# InkTime.net
KiCad netlist of a schematic drawn in EAGLE
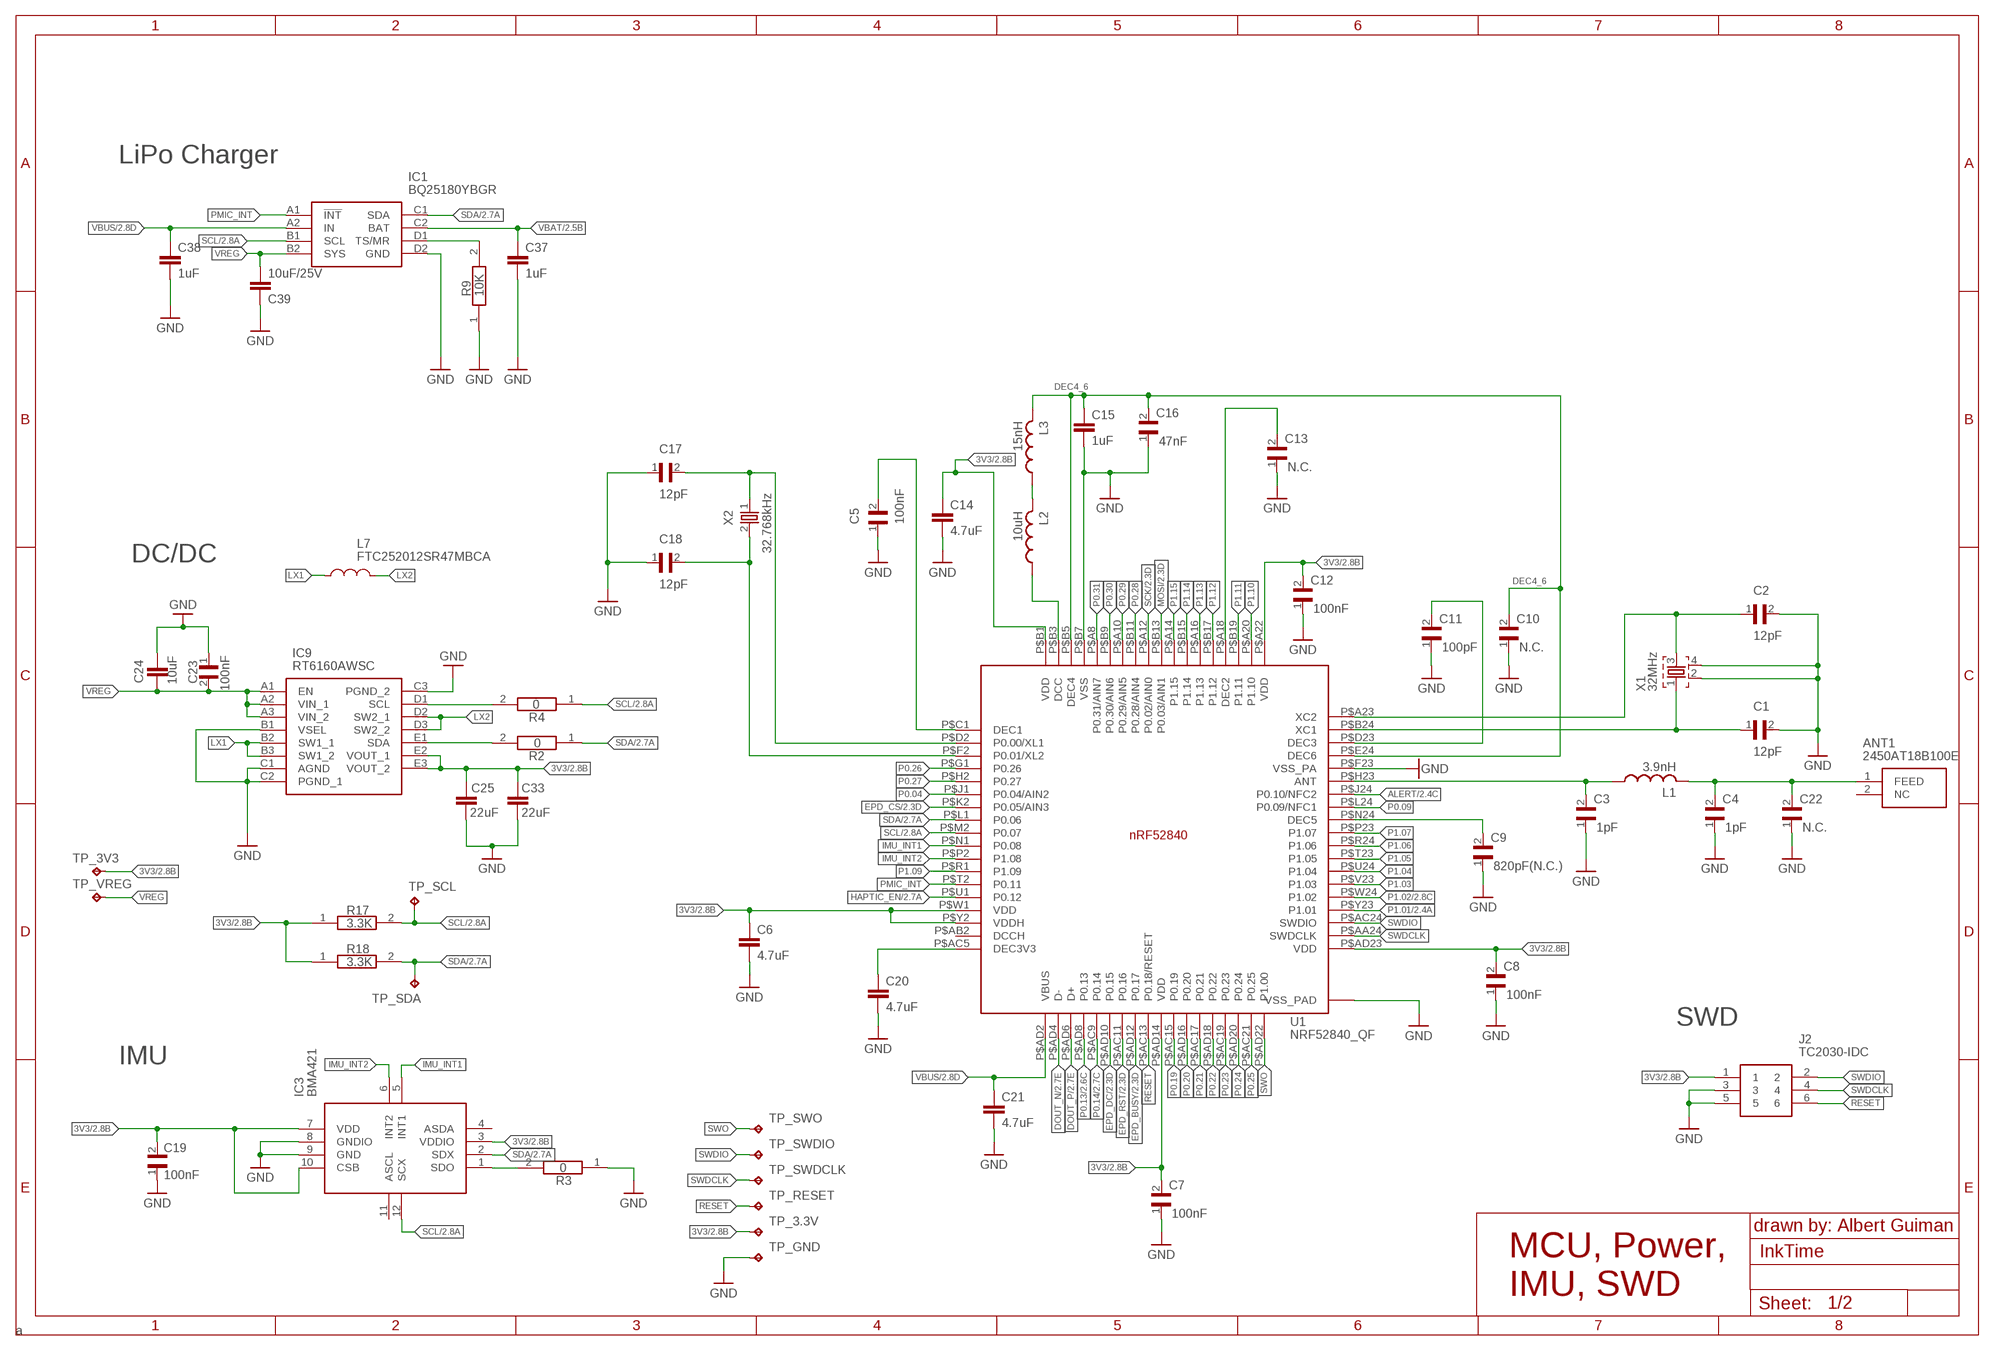
[diagram p0: schematic, sheet 1]
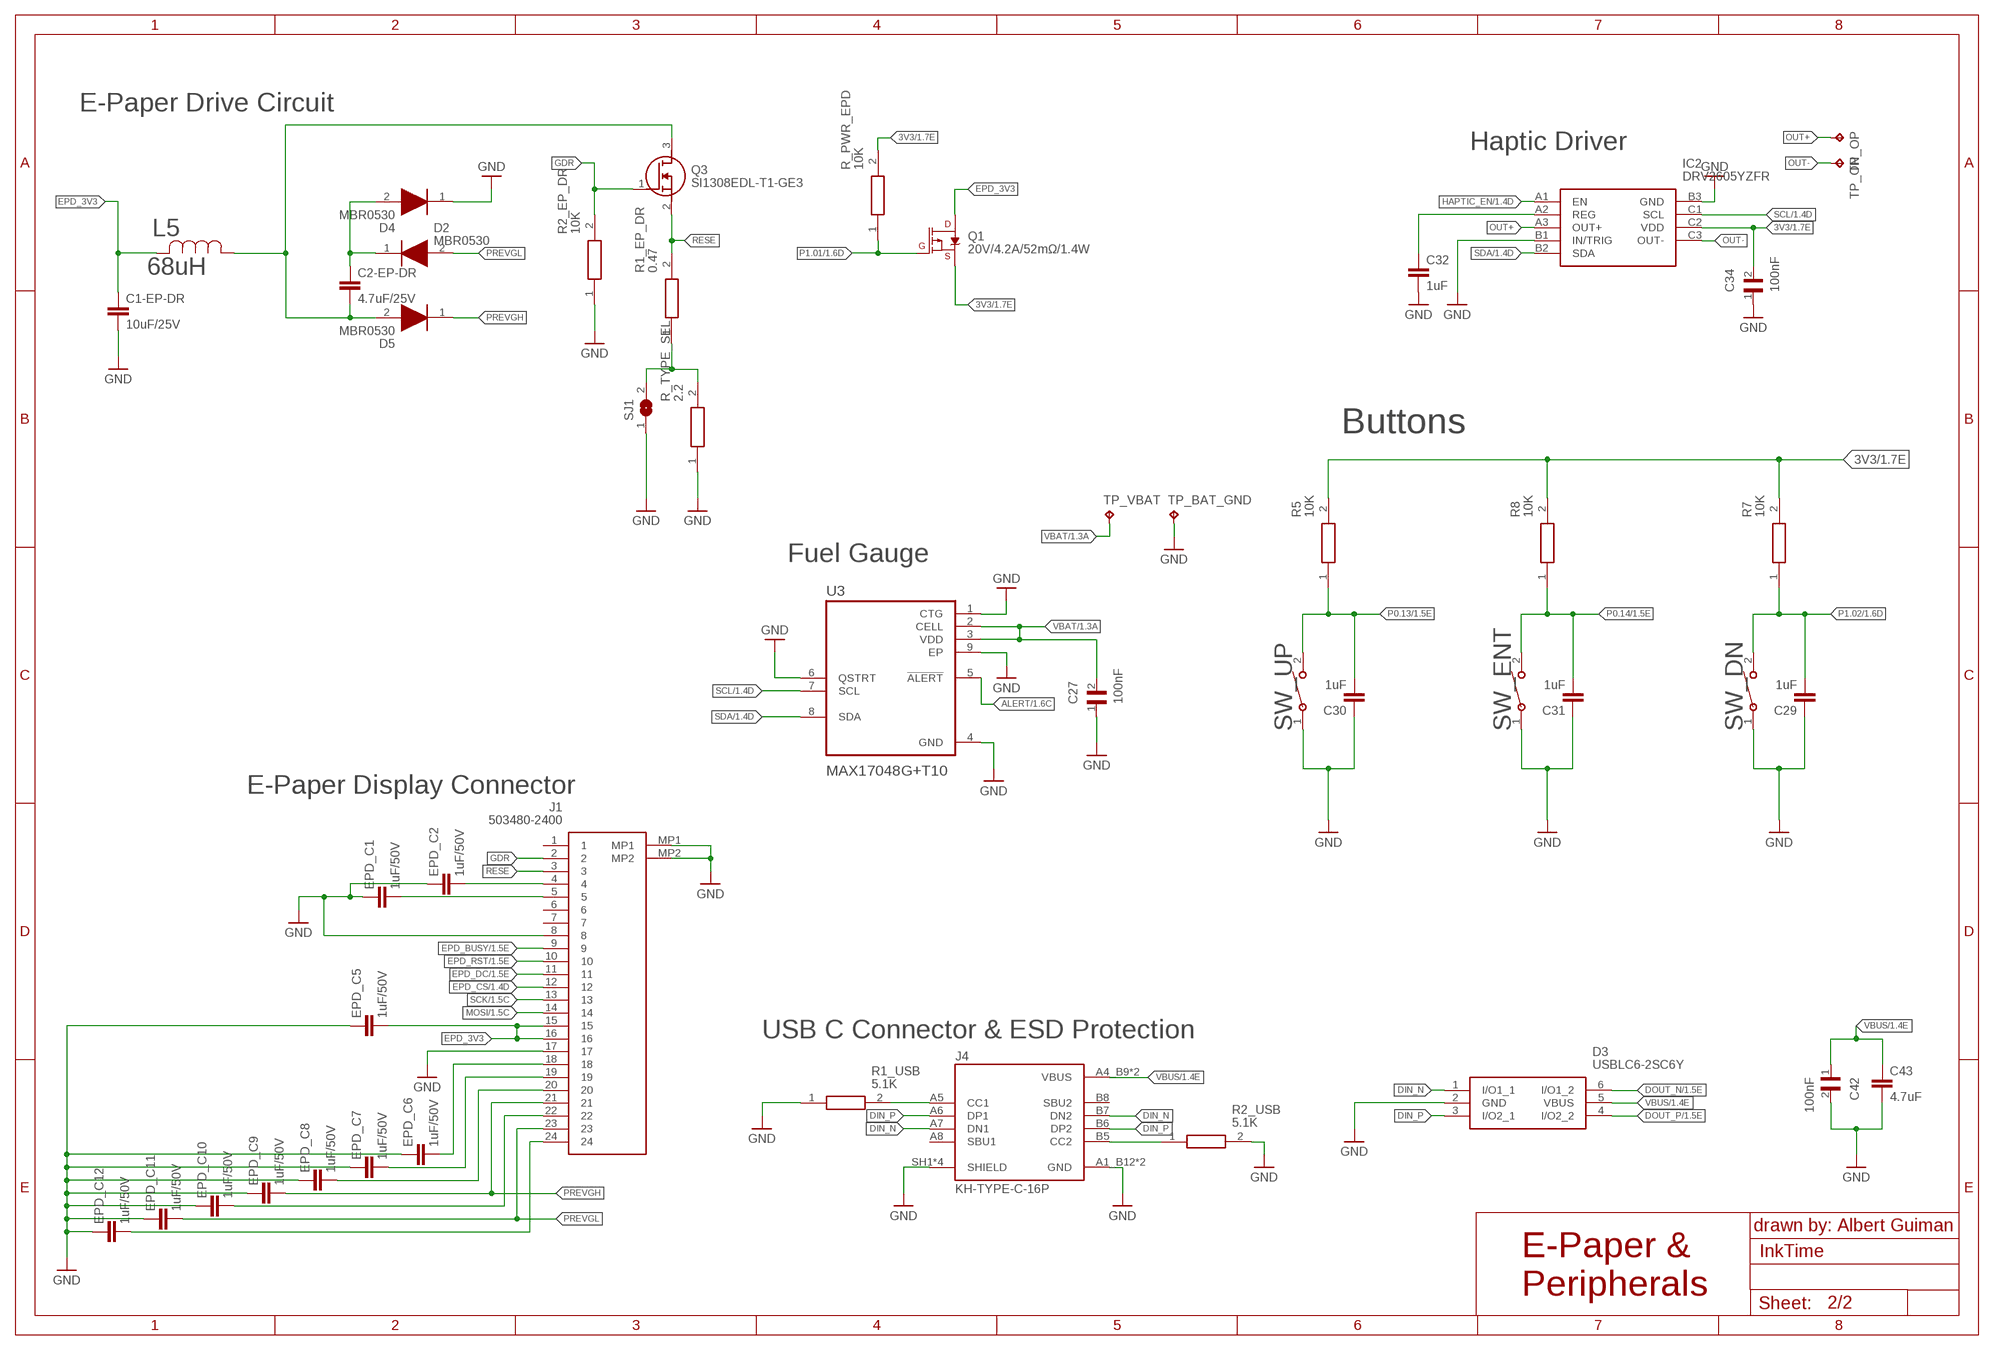
[diagram p1: schematic, sheet 2]

(export (version "E")
  (design (tool "Eeschema 10.0.6"))
  (components
    (comp (ref "C1-EP-DR")
      (value "10uF/25V")
      (footprint "eagle-import:NORDIC_NRF_3_RESC0603_N")
      (libsource (lib "eagle-import") (part "NORDIC_NRF_3_CAPACITOR_0603_N"))
    )
    (comp (ref "C2-EP-DR")
      (value "4.7uF/25V")
      (footprint "eagle-import:PERFECT_0402_0402")
      (libsource (lib "eagle-import") (part "PERFECT_0402_CAP_0402"))
    )
    (comp (ref "C27")
      (value "100nF")
      (footprint "eagle-import:GRM011R60J152KE01L_2_CAPC0201X13N")
      (fields (field (name "MF") "Murata") (field (name "MP") "GRM011R60J152KE01L"))
      (libsource (lib "eagle-import") (part "GRM011R60J152KE01L_2_GRM011R60J152KE01L"))
    )
    (comp (ref "C29")
      (value "1uF")
      (footprint "eagle-import:PERFECT_0402_0402")
      (libsource (lib "eagle-import") (part "PERFECT_0402_CAP_0402"))
    )
    (comp (ref "C30")
      (value "1uF")
      (footprint "eagle-import:PERFECT_0402_0402")
      (libsource (lib "eagle-import") (part "PERFECT_0402_CAP_0402"))
    )
    (comp (ref "C31")
      (value "1uF")
      (footprint "eagle-import:PERFECT_0402_0402")
      (libsource (lib "eagle-import") (part "PERFECT_0402_CAP_0402"))
    )
    (comp (ref "C32")
      (value "1uF")
      (footprint "eagle-import:PERFECT_0402_0402")
      (libsource (lib "eagle-import") (part "PERFECT_0402_CAP_0402"))
    )
    (comp (ref "C34")
      (value "100nF")
      (footprint "eagle-import:GRM011R60J152KE01L_2_CAPC0201X13N")
      (fields (field (name "MF") "Murata") (field (name "MP") "GRM011R60J152KE01L"))
      (libsource (lib "eagle-import") (part "GRM011R60J152KE01L_2_GRM011R60J152KE01L"))
    )
    (comp (ref "C42")
      (value "100nF")
      (footprint "eagle-import:GRM011R60J152KE01L_2_CAPC0201X13N")
      (fields (field (name "MF") "Murata") (field (name "MP") "GRM011R60J152KE01L"))
      (libsource (lib "eagle-import") (part "GRM011R60J152KE01L_2_GRM011R60J152KE01L"))
    )
    (comp (ref "C43")
      (value "4.7uF")
      (footprint "eagle-import:PERFECT_0402_0402")
      (libsource (lib "eagle-import") (part "PERFECT_0402_CAP_0402"))
    )
    (comp (ref "D2")
      (value "MBR0530")
      (footprint "eagle-import:ESP32_C6_LIBRARY_5_SOD3716X135N")
      (fields (field (name "MF") "ON Semiconductor"))
      (libsource (lib "eagle-import") (part "ESP32_C6_LIBRARY_5_MBR0530"))
    )
    (comp (ref "D3")
      (value "USBLC6-2SC6Y")
      (footprint "eagle-import:ESP32_C6_LIBRARY_3_SOT95P280X145-6N")
      (fields (field (name "MF") "STMicroelectronics"))
      (libsource (lib "eagle-import") (part "ESP32_C6_LIBRARY_3_USBLC6-2SC6Y"))
    )
    (comp (ref "D4")
      (value "MBR0530")
      (footprint "eagle-import:ESP32_C6_LIBRARY_5_SOD3716X135N")
      (fields (field (name "MF") "ON Semiconductor"))
      (libsource (lib "eagle-import") (part "ESP32_C6_LIBRARY_5_MBR0530"))
    )
    (comp (ref "D5")
      (value "MBR0530")
      (footprint "eagle-import:ESP32_C6_LIBRARY_5_SOD3716X135N")
      (fields (field (name "MF") "ON Semiconductor"))
      (libsource (lib "eagle-import") (part "ESP32_C6_LIBRARY_5_MBR0530"))
    )
    (comp (ref "EPD_C1")
      (value "1uF/50V")
      (footprint "eagle-import:PERFECT_0402_0402")
      (libsource (lib "eagle-import") (part "PERFECT_0402_CAP_0402"))
    )
    (comp (ref "EPD_C2")
      (value "1uF/50V")
      (footprint "eagle-import:PERFECT_0402_0402")
      (libsource (lib "eagle-import") (part "PERFECT_0402_CAP_0402"))
    )
    (comp (ref "EPD_C5")
      (value "1uF/50V")
      (footprint "eagle-import:PERFECT_0402_0402")
      (libsource (lib "eagle-import") (part "PERFECT_0402_CAP_0402"))
    )
    (comp (ref "EPD_C6")
      (value "1uF/50V")
      (footprint "eagle-import:PERFECT_0402_0402")
      (libsource (lib "eagle-import") (part "PERFECT_0402_CAP_0402"))
    )
    (comp (ref "EPD_C7")
      (value "1uF/50V")
      (footprint "eagle-import:PERFECT_0402_0402")
      (libsource (lib "eagle-import") (part "PERFECT_0402_CAP_0402"))
    )
    (comp (ref "EPD_C8")
      (value "1uF/50V")
      (footprint "eagle-import:PERFECT_0402_0402")
      (libsource (lib "eagle-import") (part "PERFECT_0402_CAP_0402"))
    )
    (comp (ref "EPD_C9")
      (value "1uF/50V")
      (footprint "eagle-import:PERFECT_0402_0402")
      (libsource (lib "eagle-import") (part "PERFECT_0402_CAP_0402"))
    )
    (comp (ref "EPD_C10")
      (value "1uF/50V")
      (footprint "eagle-import:PERFECT_0402_0402")
      (libsource (lib "eagle-import") (part "PERFECT_0402_CAP_0402"))
    )
    (comp (ref "EPD_C11")
      (value "1uF/50V")
      (footprint "eagle-import:PERFECT_0402_0402")
      (libsource (lib "eagle-import") (part "PERFECT_0402_CAP_0402"))
    )
    (comp (ref "EPD_C12")
      (value "1uF/50V")
      (footprint "eagle-import:PERFECT_0402_0402")
      (libsource (lib "eagle-import") (part "PERFECT_0402_CAP_0402"))
    )
    (comp (ref "IC2")
      (value "DRV2605YZFR")
      (footprint "eagle-import:DRV2605YZFR_BGA9C50P3X3_144X144X62")
      (libsource (lib "eagle-import") (part "DRV2605YZFR_DRV2605YZFR"))
    )
    (comp (ref "J1")
      (value "503480-2400")
      (footprint "eagle-import:503480-2400_5034802400")
      (fields (field (name "MOUSER_PART_NUMBER") "538-503480-2400"))
      (libsource (lib "eagle-import") (part "503480-2400_503480-2400"))
    )
    (comp (ref "J4")
      (value "KH-TYPE-C-16P")
      (footprint "eagle-import:KH-TYPE-C-16P_KINGHELM_KH-TYPE-C-16P")
      (fields (field (name "MF") "kinghelm"))
      (libsource (lib "eagle-import") (part "KH-TYPE-C-16P_KH-TYPE-C-16P"))
    )
    (comp (ref "L5")
      (value "68uH")
      (footprint "eagle-import:ESP32_C6_LIBRARY_2_IND_4828-WE-TPC_WRE")
      (fields
        (field (name "MANUFACTURER_PART_NUMBER") "744043680")
        (field (name "COPYRIGHT") "Copyright (C) 2024 Ultra Librarian. All rights reserved.")
      )
      (libsource (lib "eagle-import") (part "ESP32_C6_LIBRARY_2_744043680IND_4828-WE-TPC_WRE"))
    )
    (comp (ref "Q1")
      (value "20V/4.2A/52mΩ/1.4W")
      (footprint "eagle-import:ESP32_C6_LIBRARY_4_ESP32_C6_LIBRARY_4_ESP32_C6_LIBRARY_4_ESP32_C6_LIBRARY_4_ESP32_WROVER_SPARKFUN-DISCRETESEMI_SOT23-3")
      (libsource (lib "eagle-import") (part "ESP32_C6_LIBRARY_4_ESP32_WROVER_SPARKFUN-DISCRETESEMI_MOSFET_PCH-DMG2305UX-7"))
    )
    (comp (ref "Q3")
      (value "SI1308EDL-T1-GE3")
      (footprint "eagle-import:ESP32_C6_LIBRARY_6_SOT65P210X110-3N")
      (fields (field (name "MF") "Vishay Siliconix"))
      (libsource (lib "eagle-import") (part "ESP32_C6_LIBRARY_6_SI1308EDL-T1-GE3"))
    )
    (comp (ref "R1_EP_DR")
      (value "0.47")
      (footprint "eagle-import:ERA-1AEB3401C_0201")
      (libsource (lib "eagle-import") (part "ERA-1AEB3401C_CPF0201D7K68C1"))
    )
    (comp (ref "R1_USB")
      (value "5.1K")
      (footprint "eagle-import:ERA-1AEB3401C_0201")
      (libsource (lib "eagle-import") (part "ERA-1AEB3401C_CPF0201D7K68C1"))
    )
    (comp (ref "R2_EP_DR")
      (value "10K")
      (footprint "eagle-import:ERA-1AEB3401C_0201")
      (libsource (lib "eagle-import") (part "ERA-1AEB3401C_CPF0201D7K68C1"))
    )
    (comp (ref "R2_USB")
      (value "5.1K")
      (footprint "eagle-import:ERA-1AEB3401C_0201")
      (libsource (lib "eagle-import") (part "ERA-1AEB3401C_CPF0201D7K68C1"))
    )
    (comp (ref "R5")
      (value "10K")
      (footprint "eagle-import:ERA-1AEB3401C_0201")
      (libsource (lib "eagle-import") (part "ERA-1AEB3401C_CPF0201D7K68C1"))
    )
    (comp (ref "R7")
      (value "10K")
      (footprint "eagle-import:ERA-1AEB3401C_0201")
      (libsource (lib "eagle-import") (part "ERA-1AEB3401C_CPF0201D7K68C1"))
    )
    (comp (ref "R8")
      (value "10K")
      (footprint "eagle-import:ERA-1AEB3401C_0201")
      (libsource (lib "eagle-import") (part "ERA-1AEB3401C_CPF0201D7K68C1"))
    )
    (comp (ref "R_PWR_EPD")
      (value "10K")
      (footprint "eagle-import:ERA-1AEB3401C_0201")
      (libsource (lib "eagle-import") (part "ERA-1AEB3401C_CPF0201D7K68C1"))
    )
    (comp (ref "R_TYPE_SEL")
      (value "2.2")
      (footprint "eagle-import:ERA-1AEB3401C_0201")
      (libsource (lib "eagle-import") (part "ERA-1AEB3401C_CPF0201D7K68C1"))
    )
    (comp (ref "SJ1")
      (value "ESP32_C6_LIBRARY_7_JUMPER_SJ")
      (footprint "eagle-import:ESP32_C6_LIBRARY_7_JUMPER_SJ")
      (libsource (lib "eagle-import") (part "ESP32_C6_LIBRARY_7_JUMPER_SJ"))
    )
    (comp (ref "SW_DN")
      (value "2025-10-22_07-23-44_LIBRARY_EVP-AKE31ASW_EVP-AKE31A_PAN")
      (footprint "eagle-import:2025-10-22_07-23-44_LIBRARY_SW_EVP-AKE31A_PAN")
      (fields
        (field (name "MANUFACTURER_PART_NUMBER") "EVP-AKE31A")
        (field (name "COPYRIGHT") "Copyright (C) 2025 Ultra Librarian. All rights reserved.")
      )
      (libsource (lib "eagle-import") (part "2025-10-22_07-23-44_LIBRARY_EVP-AKE31ASW_EVP-AKE31A_PAN"))
    )
    (comp (ref "SW_ENT")
      (value "2025-10-22_07-23-44_LIBRARY_EVP-AKE31ASW_EVP-AKE31A_PAN")
      (footprint "eagle-import:2025-10-22_07-23-44_LIBRARY_SW_EVP-AKE31A_PAN")
      (fields
        (field (name "MANUFACTURER_PART_NUMBER") "EVP-AKE31A")
        (field (name "COPYRIGHT") "Copyright (C) 2025 Ultra Librarian. All rights reserved.")
      )
      (libsource (lib "eagle-import") (part "2025-10-22_07-23-44_LIBRARY_EVP-AKE31ASW_EVP-AKE31A_PAN"))
    )
    (comp (ref "SW_UP")
      (value "2025-10-22_07-23-44_LIBRARY_EVP-AKE31ASW_EVP-AKE31A_PAN")
      (footprint "eagle-import:2025-10-22_07-23-44_LIBRARY_SW_EVP-AKE31A_PAN")
      (fields
        (field (name "MANUFACTURER_PART_NUMBER") "EVP-AKE31A")
        (field (name "COPYRIGHT") "Copyright (C) 2025 Ultra Librarian. All rights reserved.")
      )
      (libsource (lib "eagle-import") (part "2025-10-22_07-23-44_LIBRARY_EVP-AKE31ASW_EVP-AKE31A_PAN"))
    )
    (comp (ref "TP_BAT_GND")
      (value "HECTOR_WATCH_1_TPTP20R")
      (footprint "eagle-import:HECTOR_WATCH_1_TP20R")
      (libsource (lib "eagle-import") (part "HECTOR_WATCH_1_TPTP20R"))
    )
    (comp (ref "TP_ON")
      (value "HECTOR_WATCH_1_TPTP20R")
      (footprint "eagle-import:HECTOR_WATCH_1_TP20R")
      (libsource (lib "eagle-import") (part "HECTOR_WATCH_1_TPTP20R"))
    )
    (comp (ref "TP_OP")
      (value "HECTOR_WATCH_1_TPTP20R")
      (footprint "eagle-import:HECTOR_WATCH_1_TP20R")
      (libsource (lib "eagle-import") (part "HECTOR_WATCH_1_TPTP20R"))
    )
    (comp (ref "TP_VBAT")
      (value "HECTOR_WATCH_1_TPTP20R")
      (footprint "eagle-import:HECTOR_WATCH_1_TP20R")
      (libsource (lib "eagle-import") (part "HECTOR_WATCH_1_TPTP20R"))
    )
    (comp (ref "U3")
      (value "MAX17048G+T10")
      (footprint "eagle-import:ESP32_C6_LIBRARY_SON50P200X200X80-9N")
      (fields (field (name "MF") "Analog Devices"))
      (libsource (lib "eagle-import") (part "ESP32_C6_LIBRARY_MAX17048G+T10"))
    )
    (comp (ref "ANT1")
      (value "2450AT18B100E")
      (footprint "eagle-import:2450AT18B100E_ANTC3216X140N")
      (fields (field (name "MOUSER_PART_NUMBER") "609-2450AT18B100E"))
      (libsource (lib "eagle-import") (part "2450AT18B100E_2450AT18B100E"))
    )
    (comp (ref "C1")
      (value "12pF")
      (footprint "eagle-import:GRM011R60J152KE01L_2_CAPC0201X13N")
      (fields (field (name "MF") "Murata") (field (name "MP") "GRM011R60J152KE01L"))
      (libsource (lib "eagle-import") (part "GRM011R60J152KE01L_2_GRM011R60J152KE01L"))
    )
    (comp (ref "C2")
      (value "12pF")
      (footprint "eagle-import:GRM011R60J152KE01L_2_CAPC0201X13N")
      (fields (field (name "MF") "Murata") (field (name "MP") "GRM011R60J152KE01L"))
      (libsource (lib "eagle-import") (part "GRM011R60J152KE01L_2_GRM011R60J152KE01L"))
    )
    (comp (ref "C3")
      (value "1pF")
      (footprint "eagle-import:GRM011R60J152KE01L_2_CAPC0201X13N")
      (fields (field (name "MF") "Murata") (field (name "MP") "GRM011R60J152KE01L"))
      (libsource (lib "eagle-import") (part "GRM011R60J152KE01L_2_GRM011R60J152KE01L"))
    )
    (comp (ref "C4")
      (value "1pF")
      (footprint "eagle-import:GRM011R60J152KE01L_2_CAPC0201X13N")
      (fields (field (name "MF") "Murata") (field (name "MP") "GRM011R60J152KE01L"))
      (libsource (lib "eagle-import") (part "GRM011R60J152KE01L_2_GRM011R60J152KE01L"))
    )
    (comp (ref "C5")
      (value "100nF")
      (footprint "eagle-import:GRM011R60J152KE01L_2_CAPC0201X13N")
      (fields (field (name "MF") "Murata") (field (name "MP") "GRM011R60J152KE01L"))
      (libsource (lib "eagle-import") (part "GRM011R60J152KE01L_2_GRM011R60J152KE01L"))
    )
    (comp (ref "C6")
      (value "4.7uF")
      (footprint "eagle-import:PERFECT_0402_0402")
      (libsource (lib "eagle-import") (part "PERFECT_0402_CAP_0402"))
    )
    (comp (ref "C7")
      (value "100nF")
      (footprint "eagle-import:GRM011R60J152KE01L_2_CAPC0201X13N")
      (fields (field (name "MF") "Murata") (field (name "MP") "GRM011R60J152KE01L"))
      (libsource (lib "eagle-import") (part "GRM011R60J152KE01L_2_GRM011R60J152KE01L"))
    )
    (comp (ref "C8")
      (value "100nF")
      (footprint "eagle-import:GRM011R60J152KE01L_2_CAPC0201X13N")
      (fields (field (name "MF") "Murata") (field (name "MP") "GRM011R60J152KE01L"))
      (libsource (lib "eagle-import") (part "GRM011R60J152KE01L_2_GRM011R60J152KE01L"))
    )
    (comp (ref "C9")
      (value "820pF(N.C.)")
      (footprint "eagle-import:GRM011R60J152KE01L_2_CAPC0201X13N")
      (fields (field (name "MF") "Murata") (field (name "MP") "GRM011R60J152KE01L"))
      (libsource (lib "eagle-import") (part "GRM011R60J152KE01L_2_GRM011R60J152KE01L"))
    )
    (comp (ref "C10")
      (value "N.C.")
      (footprint "eagle-import:GRM011R60J152KE01L_2_CAPC0201X13N")
      (fields (field (name "MF") "Murata") (field (name "MP") "GRM011R60J152KE01L"))
      (libsource (lib "eagle-import") (part "GRM011R60J152KE01L_2_GRM011R60J152KE01L"))
    )
    (comp (ref "C11")
      (value "100pF")
      (footprint "eagle-import:GRM011R60J152KE01L_2_CAPC0201X13N")
      (fields (field (name "MF") "Murata") (field (name "MP") "GRM011R60J152KE01L"))
      (libsource (lib "eagle-import") (part "GRM011R60J152KE01L_2_GRM011R60J152KE01L"))
    )
    (comp (ref "C12")
      (value "100nF")
      (footprint "eagle-import:GRM011R60J152KE01L_2_CAPC0201X13N")
      (fields (field (name "MF") "Murata") (field (name "MP") "GRM011R60J152KE01L"))
      (libsource (lib "eagle-import") (part "GRM011R60J152KE01L_2_GRM011R60J152KE01L"))
    )
    (comp (ref "C13")
      (value "N.C.")
      (footprint "eagle-import:GRM011R60J152KE01L_2_CAPC0201X13N")
      (fields (field (name "MF") "Murata") (field (name "MP") "GRM011R60J152KE01L"))
      (libsource (lib "eagle-import") (part "GRM011R60J152KE01L_2_GRM011R60J152KE01L"))
    )
    (comp (ref "C14")
      (value "4.7uF")
      (footprint "eagle-import:PERFECT_0402_0402")
      (libsource (lib "eagle-import") (part "PERFECT_0402_CAP_0402"))
    )
    (comp (ref "C15")
      (value "1uF")
      (footprint "eagle-import:PERFECT_0402_0402")
      (libsource (lib "eagle-import") (part "PERFECT_0402_CAP_0402"))
    )
    (comp (ref "C16")
      (value "47nF")
      (footprint "eagle-import:GRM011R60J152KE01L_2_CAPC0201X13N")
      (fields (field (name "MF") "Murata") (field (name "MP") "GRM011R60J152KE01L"))
      (libsource (lib "eagle-import") (part "GRM011R60J152KE01L_2_GRM011R60J152KE01L"))
    )
    (comp (ref "C17")
      (value "12pF")
      (footprint "eagle-import:GRM011R60J152KE01L_2_CAPC0201X13N")
      (fields (field (name "MF") "Murata") (field (name "MP") "GRM011R60J152KE01L"))
      (libsource (lib "eagle-import") (part "GRM011R60J152KE01L_2_GRM011R60J152KE01L"))
    )
    (comp (ref "C18")
      (value "12pF")
      (footprint "eagle-import:GRM011R60J152KE01L_2_CAPC0201X13N")
      (fields (field (name "MF") "Murata") (field (name "MP") "GRM011R60J152KE01L"))
      (libsource (lib "eagle-import") (part "GRM011R60J152KE01L_2_GRM011R60J152KE01L"))
    )
    (comp (ref "C19")
      (value "100nF")
      (footprint "eagle-import:GRM011R60J152KE01L_2_CAPC0201X13N")
      (fields (field (name "MF") "Murata") (field (name "MP") "GRM011R60J152KE01L"))
      (libsource (lib "eagle-import") (part "GRM011R60J152KE01L_2_GRM011R60J152KE01L"))
    )
    (comp (ref "C20")
      (value "4.7uF")
      (footprint "eagle-import:PERFECT_0402_0402")
      (libsource (lib "eagle-import") (part "PERFECT_0402_CAP_0402"))
    )
    (comp (ref "C21")
      (value "4.7uF")
      (footprint "eagle-import:PERFECT_0402_0402")
      (libsource (lib "eagle-import") (part "PERFECT_0402_CAP_0402"))
    )
    (comp (ref "C22")
      (value "N.C.")
      (footprint "eagle-import:GRM011R60J152KE01L_2_CAPC0201X13N")
      (fields (field (name "MF") "Murata") (field (name "MP") "GRM011R60J152KE01L"))
      (libsource (lib "eagle-import") (part "GRM011R60J152KE01L_2_GRM011R60J152KE01L"))
    )
    (comp (ref "C23")
      (value "100nF")
      (footprint "eagle-import:GRM011R60J152KE01L_2_CAPC0201X13N")
      (fields (field (name "MF") "Murata") (field (name "MP") "GRM011R60J152KE01L"))
      (libsource (lib "eagle-import") (part "GRM011R60J152KE01L_2_GRM011R60J152KE01L"))
    )
    (comp (ref "C24")
      (value "10uF")
      (footprint "eagle-import:PERFECT_0402_0402")
      (libsource (lib "eagle-import") (part "PERFECT_0402_CAP_0402"))
    )
    (comp (ref "C25")
      (value "22uF")
      (footprint "eagle-import:NORDIC_NRF_3_RESC0603_N")
      (libsource (lib "eagle-import") (part "NORDIC_NRF_3_CAPACITOR_0603_N"))
    )
    (comp (ref "C33")
      (value "22uF")
      (footprint "eagle-import:NORDIC_NRF_3_RESC0603_N")
      (libsource (lib "eagle-import") (part "NORDIC_NRF_3_CAPACITOR_0603_N"))
    )
    (comp (ref "C37")
      (value "1uF")
      (footprint "eagle-import:PERFECT_0402_0402")
      (libsource (lib "eagle-import") (part "PERFECT_0402_CAP_0402"))
    )
    (comp (ref "C38")
      (value "1uF")
      (footprint "eagle-import:PERFECT_0402_0402")
      (libsource (lib "eagle-import") (part "PERFECT_0402_CAP_0402"))
    )
    (comp (ref "C39")
      (value "10uF/25V")
      (footprint "eagle-import:NORDIC_NRF_3_RESC0603_N")
      (libsource (lib "eagle-import") (part "NORDIC_NRF_3_CAPACITOR_0603_N"))
    )
    (comp (ref "IC1")
      (value "BQ25180YBGR")
      (footprint "eagle-import:BQ25180YBGR_BGA8C40P2X4_100X155X50")
      (fields (field (name "MOUSER_PART_NUMBER") "595-BQ25180YBGR"))
      (libsource (lib "eagle-import") (part "BQ25180YBGR_BQ25180YBGR"))
    )
    (comp (ref "IC3")
      (value "BMA421")
      (footprint "eagle-import:BMA423_BMA423")
      (fields
        (field (name "MANUFACTURER_PART_NUMBER") "BMA423")
        (field (name "MOUSER_PART_NUMBER") "262-BMA423")
      )
      (libsource (lib "eagle-import") (part "BMA423_BMA423"))
    )
    (comp (ref "IC9")
      (value "RT6160AWSC")
      (footprint "eagle-import:RT6160AWSC_BGA15C40P3X5_140X230X60")
      (fields (field (name "MOUSER_PART_NUMBER") "835-RT6160AWSC"))
      (libsource (lib "eagle-import") (part "RT6160AWSC_RT6160AWSC"))
    )
    (comp (ref "J2")
      (value "TC2030-IDC")
      (footprint "eagle-import:TC2030-IDC_TC2030IDC")
      (libsource (lib "eagle-import") (part "TC2030-IDC_TC2030-IDC"))
    )
    (comp (ref "L1")
      (value "3.9nH")
      (footprint "eagle-import:NORDIC_NRF_2_RESC0201_N")
      (libsource (lib "eagle-import") (part "NORDIC_NRF_2_INDUCTOR_0201_N"))
    )
    (comp (ref "L2")
      (value "10uH")
      (footprint "eagle-import:NORDIC_NRF_2_RESC0603_N")
      (libsource (lib "eagle-import") (part "NORDIC_NRF_2_INDUCTOR_0603_N"))
    )
    (comp (ref "L3")
      (value "15nH")
      (footprint "eagle-import:NORDIC_NRF_2_RESC0402_N")
      (libsource (lib "eagle-import") (part "NORDIC_NRF_2_INDUCTOR_0402_N"))
    )
    (comp (ref "L7")
      (value "FTC252012SR47MBCA")
      (footprint "eagle-import:FTC252012SR47MBCA")
      (libsource (lib "eagle-import") (part "FTC252012SR47MBCAFTC252012SR47MBCA"))
    )
    (comp (ref "R2")
      (value "0")
      (footprint "eagle-import:ERA-1AEB3401C_0201")
      (libsource (lib "eagle-import") (part "ERA-1AEB3401C_CPF0201D7K68C1"))
    )
    (comp (ref "R3")
      (value "0")
      (footprint "eagle-import:ERA-1AEB3401C_0201")
      (libsource (lib "eagle-import") (part "ERA-1AEB3401C_CPF0201D7K68C1"))
    )
    (comp (ref "R4")
      (value "0")
      (footprint "eagle-import:ERA-1AEB3401C_0201")
      (libsource (lib "eagle-import") (part "ERA-1AEB3401C_CPF0201D7K68C1"))
    )
    (comp (ref "R9")
      (value "10K")
      (footprint "eagle-import:ERA-1AEB3401C_0201")
      (libsource (lib "eagle-import") (part "ERA-1AEB3401C_CPF0201D7K68C1"))
    )
    (comp (ref "R17")
      (value "3.3K")
      (footprint "eagle-import:ERA-1AEB3401C_0201")
      (libsource (lib "eagle-import") (part "ERA-1AEB3401C_CPF0201D7K68C1"))
    )
    (comp (ref "R18")
      (value "3.3K")
      (footprint "eagle-import:ERA-1AEB3401C_0201")
      (libsource (lib "eagle-import") (part "ERA-1AEB3401C_CPF0201D7K68C1"))
    )
    (comp (ref "TP_3.3V")
      (value "HECTOR_WATCH_1_TPTP20R")
      (footprint "eagle-import:HECTOR_WATCH_1_TP20R")
      (libsource (lib "eagle-import") (part "HECTOR_WATCH_1_TPTP20R"))
    )
    (comp (ref "TP_3V3")
      (value "HECTOR_WATCH_1_TPTP20R")
      (footprint "eagle-import:HECTOR_WATCH_1_TP20R")
      (libsource (lib "eagle-import") (part "HECTOR_WATCH_1_TPTP20R"))
    )
    (comp (ref "TP_GND")
      (value "HECTOR_WATCH_1_TPTP20R")
      (footprint "eagle-import:HECTOR_WATCH_1_TP20R")
      (libsource (lib "eagle-import") (part "HECTOR_WATCH_1_TPTP20R"))
    )
    (comp (ref "TP_RESET")
      (value "HECTOR_WATCH_1_TPTP20R")
      (footprint "eagle-import:HECTOR_WATCH_1_TP20R")
      (libsource (lib "eagle-import") (part "HECTOR_WATCH_1_TPTP20R"))
    )
    (comp (ref "TP_SCL")
      (value "HECTOR_WATCH_1_TPTP20R")
      (footprint "eagle-import:HECTOR_WATCH_1_TP20R")
      (libsource (lib "eagle-import") (part "HECTOR_WATCH_1_TPTP20R"))
    )
    (comp (ref "TP_SDA")
      (value "HECTOR_WATCH_1_TPTP20R")
      (footprint "eagle-import:HECTOR_WATCH_1_TP20R")
      (libsource (lib "eagle-import") (part "HECTOR_WATCH_1_TPTP20R"))
    )
    (comp (ref "TP_SWDCLK")
      (value "HECTOR_WATCH_1_TPTP20R")
      (footprint "eagle-import:HECTOR_WATCH_1_TP20R")
      (libsource (lib "eagle-import") (part "HECTOR_WATCH_1_TPTP20R"))
    )
    (comp (ref "TP_SWDIO")
      (value "HECTOR_WATCH_1_TPTP20R")
      (footprint "eagle-import:HECTOR_WATCH_1_TP20R")
      (libsource (lib "eagle-import") (part "HECTOR_WATCH_1_TPTP20R"))
    )
    (comp (ref "TP_SWO")
      (value "HECTOR_WATCH_1_TPTP20R")
      (footprint "eagle-import:HECTOR_WATCH_1_TP20R")
      (libsource (lib "eagle-import") (part "HECTOR_WATCH_1_TPTP20R"))
    )
    (comp (ref "TP_VREG")
      (value "HECTOR_WATCH_1_TPTP20R")
      (footprint "eagle-import:HECTOR_WATCH_1_TP20R")
      (libsource (lib "eagle-import") (part "HECTOR_WATCH_1_TPTP20R"))
    )
    (comp (ref "U1")
      (value "NRF52840_QF")
      (footprint "eagle-import:NORDIC_NRF_4_AQFN50P700X700X85_HS-74N")
      (libsource (lib "eagle-import") (part "NORDIC_NRF_4_NRF52840_QF"))
    )
    (comp (ref "X1")
      (value "32MHz")
      (footprint "eagle-import:NORDIC_NRF_BT-XTAL_2016_N")
      (libsource (lib "eagle-import") (part "NORDIC_NRF_XTAL_32MHZ"))
    )
    (comp (ref "X2")
      (value "32.768kHz")
      (footprint "eagle-import:NORDIC_NRF_1_XTAL_3215_N")
      (libsource (lib "eagle-import") (part "NORDIC_NRF_1_XTAL_32KHZ"))
    )
  )
  (nets
    (net (code "1") (name "3V3") (class "Default")
      (node (ref "C12") (pin "2") (pinfunction "2_2") (pintype "passive"))
      (node (ref "C14") (pin "1") (pinfunction "1_1") (pintype "passive"))
      (node (ref "C19") (pin "2") (pinfunction "2_2") (pintype "passive"))
      (node (ref "C25") (pin "1") (pinfunction "1_1") (pintype "passive"))
      (node (ref "C33") (pin "1") (pinfunction "1_1") (pintype "passive"))
      (node (ref "C34") (pin "2") (pinfunction "2_2") (pintype "passive"))
      (node (ref "C6") (pin "1") (pinfunction "1_1") (pintype "passive"))
      (node (ref "C7") (pin "2") (pinfunction "2_2") (pintype "passive"))
      (node (ref "C8") (pin "2") (pinfunction "2_2") (pintype "passive"))
      (node (ref "IC2") (pin "C2") (pinfunction "VDD_C2") (pintype "bidirectional"))
      (node (ref "IC3") (pin "10") (pinfunction "CSB_10") (pintype "bidirectional"))
      (node (ref "IC3") (pin "3") (pinfunction "VDDIO_3") (pintype "bidirectional"))
      (node (ref "IC3") (pin "7") (pinfunction "VDD_7") (pintype "bidirectional"))
      (node (ref "IC9") (pin "E2") (pinfunction "VOUT_1_E2") (pintype "bidirectional"))
      (node (ref "IC9") (pin "E3") (pinfunction "VOUT_2_E3") (pintype "bidirectional"))
      (node (ref "J2") (pin "1") (pinfunction "1_1") (pintype "bidirectional"))
      (node (ref "Q1") (pin "2") (pinfunction "S_2") (pintype "bidirectional"))
      (node (ref "R17") (pin "1") (pinfunction "1_1") (pintype "bidirectional"))
      (node (ref "R18") (pin "1") (pinfunction "1_1") (pintype "bidirectional"))
      (node (ref "R5") (pin "2") (pinfunction "2_2") (pintype "bidirectional"))
      (node (ref "R7") (pin "2") (pinfunction "2_2") (pintype "bidirectional"))
      (node (ref "R8") (pin "2") (pinfunction "2_2") (pintype "bidirectional"))
      (node (ref "R_PWR_EPD") (pin "2") (pinfunction "2_2") (pintype "bidirectional"))
      (node (ref "TP_3.3V") (pin "TP") (pinfunction "TP_TP") (pintype "input"))
      (node (ref "TP_3V3") (pin "TP") (pinfunction "TP_TP") (pintype "input"))
      (node (ref "U1") (pin "P$A22") (pinfunction "VDD_P$A22") (pintype "power_in"))
      (node (ref "U1") (pin "P$AD14") (pinfunction "VDD_P$AD14") (pintype "power_in"))
      (node (ref "U1") (pin "P$AD23") (pinfunction "VDD_P$AD23") (pintype "power_in"))
      (node (ref "U1") (pin "P$B1") (pinfunction "VDD_P$B1") (pintype "power_in"))
      (node (ref "U1") (pin "P$W1") (pinfunction "VDD_P$W1") (pintype "power_in"))
      (node (ref "U1") (pin "P$Y2") (pinfunction "VDDH_P$Y2") (pintype "power_in"))
    )
    (net (code "2") (name "ALERT") (class "Default")
      (node (ref "U1") (pin "P$J24") (pinfunction "P0.10/NFC2_P$J24") (pintype "bidirectional"))
      (node (ref "U3") (pin "5") (pinfunction "~{ALERT}_5") (pintype "output"))
    )
    (net (code "3") (name "DEC4_6") (class "Default")
      (node (ref "C10") (pin "2") (pinfunction "2_2") (pintype "passive"))
      (node (ref "C15") (pin "1") (pinfunction "1_1") (pintype "passive"))
      (node (ref "C16") (pin "2") (pinfunction "2_2") (pintype "passive"))
      (node (ref "L3") (pin "2") (pinfunction "2_2") (pintype "passive"))
      (node (ref "U1") (pin "P$B5") (pinfunction "DEC4_P$B5") (pintype "power_in"))
      (node (ref "U1") (pin "P$E24") (pinfunction "DEC6_P$E24") (pintype "bidirectional"))
    )
    (net (code "4") (name "DIN_N") (class "Default")
      (node (ref "D3") (pin "1") (pinfunction "I/O1_1_1") (pintype "bidirectional"))
      (node (ref "J4") (pin "A7") (pinfunction "DN1_A7") (pintype "bidirectional"))
      (node (ref "J4") (pin "B7") (pinfunction "DN2_B7") (pintype "bidirectional"))
    )
    (net (code "5") (name "DIN_P") (class "Default")
      (node (ref "D3") (pin "3") (pinfunction "I/O2_1_3") (pintype "bidirectional"))
      (node (ref "J4") (pin "A6") (pinfunction "DP1_A6") (pintype "bidirectional"))
      (node (ref "J4") (pin "B6") (pinfunction "DP2_B6") (pintype "bidirectional"))
    )
    (net (code "6") (name "DOUT_N") (class "Default")
      (node (ref "D3") (pin "6") (pinfunction "I/O1_2_6") (pintype "bidirectional"))
      (node (ref "U1") (pin "P$AD4") (pinfunction "D-_P$AD4") (pintype "bidirectional"))
    )
    (net (code "7") (name "DOUT_P") (class "Default")
      (node (ref "D3") (pin "4") (pinfunction "I/O2_2_4") (pintype "bidirectional"))
      (node (ref "U1") (pin "P$AD6") (pinfunction "D+_P$AD6") (pintype "bidirectional"))
    )
    (net (code "8") (name "EPD_3V3") (class "Default")
      (node (ref "C1-EP-DR") (pin "1") (pinfunction "1_1") (pintype "passive"))
      (node (ref "EPD_C5") (pin "2") (pinfunction "2_2") (pintype "passive"))
      (node (ref "J1") (pin "15") (pinfunction "15_15") (pintype "bidirectional"))
      (node (ref "J1") (pin "16") (pinfunction "16_16") (pintype "bidirectional"))
      (node (ref "L5") (pin "2") (pinfunction "2_2") (pintype "passive"))
      (node (ref "Q1") (pin "3") (pinfunction "D_3") (pintype "bidirectional"))
    )
    (net (code "9") (name "EPD_BUSY") (class "Default")
      (node (ref "J1") (pin "9") (pinfunction "9_9") (pintype "bidirectional"))
      (node (ref "U1") (pin "P$AD12") (pinfunction "P0.17_P$AD12") (pintype "bidirectional"))
    )
    (net (code "10") (name "EPD_CS") (class "Default")
      (node (ref "J1") (pin "12") (pinfunction "12_12") (pintype "bidirectional"))
      (node (ref "U1") (pin "P$K2") (pinfunction "P0.05/AIN3_P$K2") (pintype "bidirectional"))
    )
    (net (code "11") (name "EPD_DC") (class "Default")
      (node (ref "J1") (pin "11") (pinfunction "11_11") (pintype "bidirectional"))
      (node (ref "U1") (pin "P$AD10") (pinfunction "P0.15_P$AD10") (pintype "bidirectional"))
    )
    (net (code "12") (name "EPD_RST") (class "Default")
      (node (ref "J1") (pin "10") (pinfunction "10_10") (pintype "bidirectional"))
      (node (ref "U1") (pin "P$AC11") (pinfunction "P0.16_P$AC11") (pintype "bidirectional"))
    )
    (net (code "13") (name "GDR") (class "Default")
      (node (ref "J1") (pin "2") (pinfunction "2_2") (pintype "bidirectional"))
      (node (ref "Q3") (pin "1") (pinfunction "G_1") (pintype "bidirectional"))
      (node (ref "R2_EP_DR") (pin "2") (pinfunction "2_2") (pintype "bidirectional"))
    )
    (net (code "14") (name "GND") (class "Default")
      (node (ref "C1") (pin "2") (pinfunction "2_2") (pintype "passive"))
      (node (ref "C1-EP-DR") (pin "2") (pinfunction "2_2") (pintype "passive"))
      (node (ref "C10") (pin "1") (pinfunction "1_1") (pintype "passive"))
      (node (ref "C11") (pin "1") (pinfunction "1_1") (pintype "passive"))
      (node (ref "C12") (pin "1") (pinfunction "1_1") (pintype "passive"))
      (node (ref "C13") (pin "1") (pinfunction "1_1") (pintype "passive"))
      (node (ref "C14") (pin "2") (pinfunction "2_2") (pintype "passive"))
      (node (ref "C15") (pin "2") (pinfunction "2_2") (pintype "passive"))
      (node (ref "C16") (pin "1") (pinfunction "1_1") (pintype "passive"))
      (node (ref "C17") (pin "1") (pinfunction "1_1") (pintype "passive"))
      (node (ref "C18") (pin "1") (pinfunction "1_1") (pintype "passive"))
      (node (ref "C19") (pin "1") (pinfunction "1_1") (pintype "passive"))
      (node (ref "C2") (pin "2") (pinfunction "2_2") (pintype "passive"))
      (node (ref "C20") (pin "2") (pinfunction "2_2") (pintype "passive"))
      (node (ref "C21") (pin "2") (pinfunction "2_2") (pintype "passive"))
      (node (ref "C22") (pin "1") (pinfunction "1_1") (pintype "passive"))
      (node (ref "C23") (pin "1") (pinfunction "1_1") (pintype "passive"))
      (node (ref "C24") (pin "1") (pinfunction "1_1") (pintype "passive"))
      (node (ref "C25") (pin "2") (pinfunction "2_2") (pintype "passive"))
      (node (ref "C27") (pin "1") (pinfunction "1_1") (pintype "passive"))
      (node (ref "C29") (pin "1") (pinfunction "1_1") (pintype "passive"))
      (node (ref "C3") (pin "1") (pinfunction "1_1") (pintype "passive"))
      (node (ref "C30") (pin "1") (pinfunction "1_1") (pintype "passive"))
      (node (ref "C31") (pin "1") (pinfunction "1_1") (pintype "passive"))
      (node (ref "C32") (pin "2") (pinfunction "2_2") (pintype "passive"))
      (node (ref "C33") (pin "2") (pinfunction "2_2") (pintype "passive"))
      (node (ref "C34") (pin "1") (pinfunction "1_1") (pintype "passive"))
      (node (ref "C37") (pin "2") (pinfunction "2_2") (pintype "passive"))
      (node (ref "C38") (pin "2") (pinfunction "2_2") (pintype "passive"))
      (node (ref "C39") (pin "2") (pinfunction "2_2") (pintype "passive"))
      (node (ref "C4") (pin "1") (pinfunction "1_1") (pintype "passive"))
      (node (ref "C42") (pin "2") (pinfunction "2_2") (pintype "passive"))
      (node (ref "C43") (pin "2") (pinfunction "2_2") (pintype "passive"))
      (node (ref "C5") (pin "1") (pinfunction "1_1") (pintype "passive"))
      (node (ref "C6") (pin "2") (pinfunction "2_2") (pintype "passive"))
      (node (ref "C7") (pin "1") (pinfunction "1_1") (pintype "passive"))
      (node (ref "C8") (pin "1") (pinfunction "1_1") (pintype "passive"))
      (node (ref "C9") (pin "1") (pinfunction "1_1") (pintype "passive"))
      (node (ref "D3") (pin "2") (pinfunction "GND_2") (pintype "bidirectional"))
      (node (ref "D4") (pin "1") (pinfunction "K_1") (pintype "bidirectional"))
      (node (ref "EPD_C1") (pin "1") (pinfunction "1_1") (pintype "passive"))
      (node (ref "EPD_C10") (pin "1") (pinfunction "1_1") (pintype "passive"))
      (node (ref "EPD_C11") (pin "1") (pinfunction "1_1") (pintype "passive"))
      (node (ref "EPD_C12") (pin "1") (pinfunction "1_1") (pintype "passive"))
      (node (ref "EPD_C2") (pin "1") (pinfunction "1_1") (pintype "passive"))
      (node (ref "EPD_C5") (pin "1") (pinfunction "1_1") (pintype "passive"))
      (node (ref "EPD_C6") (pin "1") (pinfunction "1_1") (pintype "passive"))
      (node (ref "EPD_C7") (pin "1") (pinfunction "1_1") (pintype "passive"))
      (node (ref "EPD_C8") (pin "1") (pinfunction "1_1") (pintype "passive"))
      (node (ref "EPD_C9") (pin "1") (pinfunction "1_1") (pintype "passive"))
      (node (ref "IC1") (pin "D2") (pinfunction "GND_D2") (pintype "bidirectional"))
      (node (ref "IC2") (pin "B1") (pinfunction "IN/TRIG_B1") (pintype "bidirectional"))
      (node (ref "IC2") (pin "B3") (pinfunction "GND_B3") (pintype "bidirectional"))
      (node (ref "IC3") (pin "8") (pinfunction "GNDIO_8") (pintype "bidirectional"))
      (node (ref "IC3") (pin "9") (pinfunction "GND_9") (pintype "bidirectional"))
      (node (ref "IC9") (pin "B1") (pinfunction "VSEL_B1") (pintype "bidirectional"))
      (node (ref "IC9") (pin "C1") (pinfunction "AGND_C1") (pintype "bidirectional"))
      (node (ref "IC9") (pin "C2") (pinfunction "PGND_1_C2") (pintype "bidirectional"))
      (node (ref "IC9") (pin "C3") (pinfunction "PGND_2_C3") (pintype "bidirectional"))
      (node (ref "J1") (pin "17") (pinfunction "17_17") (pintype "bidirectional"))
      (node (ref "J1") (pin "8") (pinfunction "8_8") (pintype "bidirectional"))
      (node (ref "J1") (pin "MP1") (pinfunction "MP1_MP1") (pintype "bidirectional"))
      (node (ref "J1") (pin "MP2") (pinfunction "MP2_MP2") (pintype "bidirectional"))
      (node (ref "J2") (pin "3") (pinfunction "3_3") (pintype "bidirectional"))
      (node (ref "J2") (pin "5") (pinfunction "5_5") (pintype "bidirectional"))
      (node (ref "J4") (pin "A12_B1") (pinfunction "GND_A12_B1") (pintype "power_in"))
      (node (ref "J4") (pin "A1_B12") (pinfunction "GND_A1_B12") (pintype "power_in"))
      (node (ref "J4") (pin "SH1") (pinfunction "SHIELD_SH1") (pintype "passive"))
      (node (ref "J4") (pin "SH2") (pinfunction "SHIELD_SH2") (pintype "passive"))
      (node (ref "J4") (pin "SH3") (pinfunction "SHIELD_SH3") (pintype "passive"))
      (node (ref "J4") (pin "SH4") (pinfunction "SHIELD_SH4") (pintype "passive"))
      (node (ref "R1_USB") (pin "1") (pinfunction "1_1") (pintype "bidirectional"))
      (node (ref "R2_EP_DR") (pin "1") (pinfunction "1_1") (pintype "bidirectional"))
      (node (ref "R2_USB") (pin "2") (pinfunction "2_2") (pintype "bidirectional"))
      (node (ref "R3") (pin "1") (pinfunction "1_1") (pintype "bidirectional"))
      (node (ref "R9") (pin "1") (pinfunction "1_1") (pintype "bidirectional"))
      (node (ref "R_TYPE_SEL") (pin "1") (pinfunction "1_1") (pintype "bidirectional"))
      (node (ref "SJ1") (pin "1") (pinfunction "1_1") (pintype "passive"))
      (node (ref "SW_DN") (pin "1") (pinfunction "1_1") (pintype "passive"))
      (node (ref "SW_ENT") (pin "1") (pinfunction "1_1") (pintype "passive"))
      (node (ref "SW_UP") (pin "1") (pinfunction "1_1") (pintype "passive"))
      (node (ref "TP_BAT_GND") (pin "TP") (pinfunction "TP_TP") (pintype "input"))
      (node (ref "TP_GND") (pin "TP") (pinfunction "TP_TP") (pintype "input"))
      (node (ref "U1") (pin "P$74") (pinfunction "VSS_PAD_P$74") (pintype "bidirectional"))
      (node (ref "U1") (pin "P$75") (pinfunction "VSS_PAD_P$75") (pintype "bidirectional"))
      (node (ref "U1") (pin "P$76") (pinfunction "VSS_PAD_P$76") (pintype "bidirectional"))
      (node (ref "U1") (pin "P$77") (pinfunction "VSS_PAD_P$77") (pintype "bidirectional"))
      (node (ref "U1") (pin "P$78") (pinfunction "VSS_PAD_P$78") (pintype "bidirectional"))
      (node (ref "U1") (pin "P$79") (pinfunction "VSS_PAD_P$79") (pintype "bidirectional"))
      (node (ref "U1") (pin "P$80") (pinfunction "VSS_PAD_P$80") (pintype "bidirectional"))
      (node (ref "U1") (pin "P$81") (pinfunction "VSS_PAD_P$81") (pintype "bidirectional"))
      (node (ref "U1") (pin "P$82") (pinfunction "VSS_PAD_P$82") (pintype "bidirectional"))
      (node (ref "U1") (pin "P$83") (pinfunction "VSS_PAD_P$83") (pintype "bidirectional"))
      (node (ref "U1") (pin "P$84") (pinfunction "VSS_PAD_P$84") (pintype "bidirectional"))
      (node (ref "U1") (pin "P$85") (pinfunction "VSS_PAD_P$85") (pintype "bidirectional"))
      (node (ref "U1") (pin "P$86") (pinfunction "VSS_PAD_P$86") (pintype "bidirectional"))
      (node (ref "U1") (pin "P$87") (pinfunction "VSS_PAD_P$87") (pintype "bidirectional"))
      (node (ref "U1") (pin "P$88") (pinfunction "VSS_PAD_P$88") (pintype "bidirectional"))
      (node (ref "U1") (pin "P$89") (pinfunction "VSS_PAD_P$89") (pintype "bidirectional"))
      (node (ref "U1") (pin "P$90") (pinfunction "VSS_PAD_P$90") (pintype "bidirectional"))
      (node (ref "U1") (pin "P$B7") (pinfunction "VSS_P$B7") (pintype "power_in"))
      (node (ref "U1") (pin "P$F23") (pinfunction "VSS_PA_P$F23") (pintype "bidirectional"))
      (node (ref "U3") (pin "1") (pinfunction "CTG_1") (pintype "power_in"))
      (node (ref "U3") (pin "4") (pinfunction "GND_4") (pintype "power_in"))
      (node (ref "U3") (pin "6") (pinfunction "QSTRT_6") (pintype "input"))
      (node (ref "U3") (pin "9") (pinfunction "EP_9") (pintype "power_in"))
      (node (ref "X1") (pin "2") (pinfunction "2_2") (pintype "passive"))
      (node (ref "X1") (pin "4") (pinfunction "4_4") (pintype "passive"))
    )
    (net (code "15") (name "HAPTIC_EN") (class "Default")
      (node (ref "IC2") (pin "A1") (pinfunction "EN_A1") (pintype "bidirectional"))
      (node (ref "U1") (pin "P$U1") (pinfunction "P0.12_P$U1") (pintype "bidirectional"))
    )
    (net (code "16") (name "IMU_INT1") (class "Default")
      (node (ref "IC3") (pin "5") (pinfunction "INT1_5") (pintype "bidirectional"))
      (node (ref "U1") (pin "P$N1") (pinfunction "P0.08_P$N1") (pintype "bidirectional"))
    )
    (net (code "17") (name "IMU_INT2") (class "Default")
      (node (ref "IC3") (pin "6") (pinfunction "INT2_6") (pintype "bidirectional"))
      (node (ref "U1") (pin "P$P2") (pinfunction "P1.08_P$P2") (pintype "bidirectional"))
    )
    (net (code "18") (name "LX1") (class "Default")
      (node (ref "IC9") (pin "B2") (pinfunction "SW1_1_B2") (pintype "bidirectional"))
      (node (ref "IC9") (pin "B3") (pinfunction "SW1_2_B3") (pintype "bidirectional"))
      (node (ref "L7") (pin "1") (pinfunction "1_1") (pintype "passive"))
    )
    (net (code "19") (name "LX2") (class "Default")
      (node (ref "IC9") (pin "D2") (pinfunction "SW2_1_D2") (pintype "bidirectional"))
      (node (ref "IC9") (pin "D3") (pinfunction "SW2_2_D3") (pintype "bidirectional"))
      (node (ref "L7") (pin "2") (pinfunction "2_2") (pintype "passive"))
    )
    (net (code "20") (name "MOSI") (class "Default")
      (node (ref "J1") (pin "14") (pinfunction "14_14") (pintype "bidirectional"))
      (node (ref "U1") (pin "P$B13") (pinfunction "P0.03/AIN1_P$B13") (pintype "bidirectional"))
    )
    (net (code "21") (name "Net-(ANT1-FEED)") (class "Default")
      (node (ref "ANT1") (pin "1") (pinfunction "FEED_1") (pintype "input"))
      (node (ref "C22") (pin "2") (pinfunction "2_2") (pintype "passive"))
      (node (ref "C4") (pin "2") (pinfunction "2_2") (pintype "passive"))
      (node (ref "L1") (pin "2") (pinfunction "2_2") (pintype "passive"))
    )
    (net (code "22") (name "Net-(D2-K)") (class "Default")
      (node (ref "C2-EP-DR") (pin "1") (pinfunction "1_1") (pintype "passive"))
      (node (ref "D2") (pin "1") (pinfunction "K_1") (pintype "bidirectional"))
      (node (ref "D4") (pin "2") (pinfunction "A_2") (pintype "bidirectional"))
    )
    (net (code "23") (name "Net-(D5-A)") (class "Default")
      (node (ref "C2-EP-DR") (pin "2") (pinfunction "2_2") (pintype "passive"))
      (node (ref "D5") (pin "2") (pinfunction "A_2") (pintype "bidirectional"))
      (node (ref "L5") (pin "1") (pinfunction "1_1") (pintype "passive"))
      (node (ref "Q3") (pin "3") (pinfunction "D_3") (pintype "bidirectional"))
    )
    (net (code "24") (name "Net-(EPD_C1-Pad2)") (class "Default")
      (node (ref "EPD_C1") (pin "2") (pinfunction "2_2") (pintype "passive"))
      (node (ref "J1") (pin "5") (pinfunction "5_5") (pintype "bidirectional"))
    )
    (net (code "25") (name "Net-(EPD_C2-Pad2)") (class "Default")
      (node (ref "EPD_C2") (pin "2") (pinfunction "2_2") (pintype "passive"))
      (node (ref "J1") (pin "4") (pinfunction "4_4") (pintype "bidirectional"))
    )
    (net (code "26") (name "Net-(EPD_C6-Pad2)") (class "Default")
      (node (ref "EPD_C6") (pin "2") (pinfunction "2_2") (pintype "passive"))
      (node (ref "J1") (pin "18") (pinfunction "18_18") (pintype "bidirectional"))
    )
    (net (code "27") (name "Net-(EPD_C7-Pad2)") (class "Default")
      (node (ref "EPD_C7") (pin "2") (pinfunction "2_2") (pintype "passive"))
      (node (ref "J1") (pin "19") (pinfunction "19_19") (pintype "bidirectional"))
    )
    (net (code "28") (name "Net-(EPD_C8-Pad2)") (class "Default")
      (node (ref "EPD_C8") (pin "2") (pinfunction "2_2") (pintype "passive"))
      (node (ref "J1") (pin "20") (pinfunction "20_20") (pintype "bidirectional"))
    )
    (net (code "29") (name "Net-(EPD_C10-Pad2)") (class "Default")
      (node (ref "EPD_C10") (pin "2") (pinfunction "2_2") (pintype "passive"))
      (node (ref "J1") (pin "22") (pinfunction "22_22") (pintype "bidirectional"))
    )
    (net (code "30") (name "Net-(EPD_C12-Pad2)") (class "Default")
      (node (ref "EPD_C12") (pin "2") (pinfunction "2_2") (pintype "passive"))
      (node (ref "J1") (pin "24") (pinfunction "24_24") (pintype "bidirectional"))
    )
    (net (code "31") (name "Net-(IC1-TS{slash}MR)") (class "Default")
      (node (ref "IC1") (pin "D1") (pinfunction "TS/MR_D1") (pintype "bidirectional"))
      (node (ref "R9") (pin "2") (pinfunction "2_2") (pintype "bidirectional"))
    )
    (net (code "32") (name "Net-(IC2-REG)") (class "Default")
      (node (ref "C32") (pin "1") (pinfunction "1_1") (pintype "passive"))
      (node (ref "IC2") (pin "A2") (pinfunction "REG_A2") (pintype "bidirectional"))
    )
    (net (code "33") (name "Net-(IC3-SDO)") (class "Default")
      (node (ref "IC3") (pin "1") (pinfunction "SDO_1") (pintype "bidirectional"))
      (node (ref "R3") (pin "2") (pinfunction "2_2") (pintype "bidirectional"))
    )
    (net (code "34") (name "Net-(IC9-SCL)") (class "Default")
      (node (ref "IC9") (pin "D1") (pinfunction "SCL_D1") (pintype "bidirectional"))
      (node (ref "R4") (pin "2") (pinfunction "2_2") (pintype "bidirectional"))
    )
    (net (code "35") (name "Net-(IC9-SDA)") (class "Default")
      (node (ref "IC9") (pin "E1") (pinfunction "SDA_E1") (pintype "bidirectional"))
      (node (ref "R2") (pin "2") (pinfunction "2_2") (pintype "bidirectional"))
    )
    (net (code "36") (name "Net-(J4-CC1)") (class "Default")
      (node (ref "J4") (pin "A5") (pinfunction "CC1_A5") (pintype "bidirectional"))
      (node (ref "R1_USB") (pin "2") (pinfunction "2_2") (pintype "bidirectional"))
    )
    (net (code "37") (name "Net-(J4-CC2)") (class "Default")
      (node (ref "J4") (pin "B5") (pinfunction "CC2_B5") (pintype "bidirectional"))
      (node (ref "R2_USB") (pin "1") (pinfunction "1_1") (pintype "bidirectional"))
    )
    (net (code "38") (name "Net-(L2-Pad2)") (class "Default")
      (node (ref "L2") (pin "2") (pinfunction "2_2") (pintype "passive"))
      (node (ref "L3") (pin "1") (pinfunction "1_1") (pintype "passive"))
    )
    (net (code "39") (name "Net-(R1_EP_DR-Pad1)") (class "Default")
      (node (ref "R1_EP_DR") (pin "1") (pinfunction "1_1") (pintype "bidirectional"))
      (node (ref "R_TYPE_SEL") (pin "2") (pinfunction "2_2") (pintype "bidirectional"))
      (node (ref "SJ1") (pin "2") (pinfunction "2_2") (pintype "passive"))
    )
    (net (code "40") (name "Net-(U1-ANT)") (class "Default")
      (node (ref "C3") (pin "2") (pinfunction "2_2") (pintype "passive"))
      (node (ref "L1") (pin "1") (pinfunction "1_1") (pintype "passive"))
      (node (ref "U1") (pin "P$H23") (pinfunction "ANT_P$H23") (pintype "bidirectional"))
    )
    (net (code "41") (name "Net-(U1-DCC)") (class "Default")
      (node (ref "L2") (pin "1") (pinfunction "1_1") (pintype "passive"))
      (node (ref "U1") (pin "P$B3") (pinfunction "DCC_P$B3") (pintype "output"))
    )
    (net (code "42") (name "Net-(U1-DEC1)") (class "Default")
      (node (ref "C5") (pin "2") (pinfunction "2_2") (pintype "passive"))
      (node (ref "U1") (pin "P$C1") (pinfunction "DEC1_P$C1") (pintype "power_in"))
    )
    (net (code "43") (name "Net-(U1-DEC2)") (class "Default")
      (node (ref "C13") (pin "2") (pinfunction "2_2") (pintype "passive"))
      (node (ref "U1") (pin "P$A18") (pinfunction "DEC2_P$A18") (pintype "bidirectional"))
    )
    (net (code "44") (name "Net-(U1-DEC3)") (class "Default")
      (node (ref "C11") (pin "2") (pinfunction "2_2") (pintype "passive"))
      (node (ref "U1") (pin "P$D23") (pinfunction "DEC3_P$D23") (pintype "bidirectional"))
    )
    (net (code "45") (name "Net-(U1-DEC3V3)") (class "Default")
      (node (ref "C20") (pin "1") (pinfunction "1_1") (pintype "passive"))
      (node (ref "U1") (pin "P$AC5") (pinfunction "DEC3V3_P$AC5") (pintype "bidirectional"))
    )
    (net (code "46") (name "Net-(U1-DEC5)") (class "Default")
      (node (ref "C9") (pin "2") (pinfunction "2_2") (pintype "passive"))
      (node (ref "U1") (pin "P$N24") (pinfunction "DEC5_P$N24") (pintype "bidirectional"))
    )
    (net (code "47") (name "Net-(U1-P0.00{slash}XL1)") (class "Default")
      (node (ref "C17") (pin "2") (pinfunction "2_2") (pintype "passive"))
      (node (ref "U1") (pin "P$D2") (pinfunction "P0.00/XL1_P$D2") (pintype "bidirectional"))
      (node (ref "X2") (pin "1") (pinfunction "1_1") (pintype "passive"))
    )
    (net (code "48") (name "Net-(U1-P0.01{slash}XL2)") (class "Default")
      (node (ref "C18") (pin "2") (pinfunction "2_2") (pintype "passive"))
      (node (ref "U1") (pin "P$F2") (pinfunction "P0.01/XL2_P$F2") (pintype "bidirectional"))
      (node (ref "X2") (pin "2") (pinfunction "2_2") (pintype "passive"))
    )
    (net (code "49") (name "Net-(U1-XC1)") (class "Default")
      (node (ref "C1") (pin "1") (pinfunction "1_1") (pintype "passive"))
      (node (ref "U1") (pin "P$B24") (pinfunction "XC1_P$B24") (pintype "input"))
      (node (ref "X1") (pin "1") (pinfunction "1_1") (pintype "passive"))
    )
    (net (code "50") (name "Net-(U1-XC2)") (class "Default")
      (node (ref "C2") (pin "1") (pinfunction "1_1") (pintype "passive"))
      (node (ref "U1") (pin "P$A23") (pinfunction "XC2_P$A23") (pintype "output"))
      (node (ref "X1") (pin "3") (pinfunction "3_3") (pintype "passive"))
    )
    (net (code "51") (name "OUT+") (class "Default")
      (node (ref "IC2") (pin "A3") (pinfunction "OUT+_A3") (pintype "bidirectional"))
      (node (ref "TP_OP") (pin "TP") (pinfunction "TP_TP") (pintype "input"))
    )
    (net (code "52") (name "OUT-") (class "Default")
      (node (ref "IC2") (pin "C3") (pinfunction "OUT-_C3") (pintype "bidirectional"))
      (node (ref "TP_ON") (pin "TP") (pinfunction "TP_TP") (pintype "input"))
    )
    (net (code "53") (name "P0.04") (class "Default")
      (node (ref "U1") (pin "P$J1") (pinfunction "P0.04/AIN2_P$J1") (pintype "bidirectional"))
    )
    (net (code "54") (name "P0.09") (class "Default")
      (node (ref "U1") (pin "P$L24") (pinfunction "P0.09/NFC1_P$L24") (pintype "bidirectional"))
    )
    (net (code "55") (name "P0.13") (class "Default")
      (node (ref "C30") (pin "2") (pinfunction "2_2") (pintype "passive"))
      (node (ref "R5") (pin "1") (pinfunction "1_1") (pintype "bidirectional"))
      (node (ref "SW_UP") (pin "2") (pinfunction "2_2") (pintype "passive"))
      (node (ref "U1") (pin "P$AD8") (pinfunction "P0.13_P$AD8") (pintype "bidirectional"))
    )
    (net (code "56") (name "P0.14") (class "Default")
      (node (ref "C31") (pin "2") (pinfunction "2_2") (pintype "passive"))
      (node (ref "R8") (pin "1") (pinfunction "1_1") (pintype "bidirectional"))
      (node (ref "SW_ENT") (pin "2") (pinfunction "2_2") (pintype "passive"))
      (node (ref "U1") (pin "P$AC9") (pinfunction "P0.14_P$AC9") (pintype "bidirectional"))
    )
    (net (code "57") (name "P0.19") (class "Default")
      (node (ref "U1") (pin "P$AC15") (pinfunction "P0.19_P$AC15") (pintype "bidirectional"))
    )
    (net (code "58") (name "P0.20") (class "Default")
      (node (ref "U1") (pin "P$AD16") (pinfunction "P0.20_P$AD16") (pintype "bidirectional"))
    )
    (net (code "59") (name "P0.21") (class "Default")
      (node (ref "U1") (pin "P$AC17") (pinfunction "P0.21_P$AC17") (pintype "bidirectional"))
    )
    (net (code "60") (name "P0.22") (class "Default")
      (node (ref "U1") (pin "P$AD18") (pinfunction "P0.22_P$AD18") (pintype "bidirectional"))
    )
    (net (code "61") (name "P0.23") (class "Default")
      (node (ref "U1") (pin "P$AC19") (pinfunction "P0.23_P$AC19") (pintype "bidirectional"))
    )
    (net (code "62") (name "P0.24") (class "Default")
      (node (ref "U1") (pin "P$AD20") (pinfunction "P0.24_P$AD20") (pintype "bidirectional"))
    )
    (net (code "63") (name "P0.25") (class "Default")
      (node (ref "U1") (pin "P$AC21") (pinfunction "P0.25_P$AC21") (pintype "bidirectional"))
    )
    (net (code "64") (name "P0.26") (class "Default")
      (node (ref "U1") (pin "P$G1") (pinfunction "P0.26_P$G1") (pintype "bidirectional"))
    )
    (net (code "65") (name "P0.27") (class "Default")
      (node (ref "U1") (pin "P$H2") (pinfunction "P0.27_P$H2") (pintype "bidirectional"))
    )
    (net (code "66") (name "P0.28") (class "Default")
      (node (ref "U1") (pin "P$B11") (pinfunction "P0.28/AIN4_P$B11") (pintype "bidirectional"))
    )
    (net (code "67") (name "P0.29") (class "Default")
      (node (ref "U1") (pin "P$A10") (pinfunction "P0.29/AIN5_P$A10") (pintype "bidirectional"))
    )
    (net (code "68") (name "P0.30") (class "Default")
      (node (ref "U1") (pin "P$B9") (pinfunction "P0.30/AIN6_P$B9") (pintype "bidirectional"))
    )
    (net (code "69") (name "P0.31") (class "Default")
      (node (ref "U1") (pin "P$A8") (pinfunction "P0.31/AIN7_P$A8") (pintype "bidirectional"))
    )
    (net (code "70") (name "P1.01") (class "Default")
      (node (ref "Q1") (pin "1") (pinfunction "G_1") (pintype "bidirectional"))
      (node (ref "R_PWR_EPD") (pin "1") (pinfunction "1_1") (pintype "bidirectional"))
      (node (ref "U1") (pin "P$Y23") (pinfunction "P1.01_P$Y23") (pintype "bidirectional"))
    )
    (net (code "71") (name "P1.02") (class "Default")
      (node (ref "C29") (pin "2") (pinfunction "2_2") (pintype "passive"))
      (node (ref "R7") (pin "1") (pinfunction "1_1") (pintype "bidirectional"))
      (node (ref "SW_DN") (pin "2") (pinfunction "2_2") (pintype "passive"))
      (node (ref "U1") (pin "P$W24") (pinfunction "P1.02_P$W24") (pintype "bidirectional"))
    )
    (net (code "72") (name "P1.03") (class "Default")
      (node (ref "U1") (pin "P$V23") (pinfunction "P1.03_P$V23") (pintype "bidirectional"))
    )
    (net (code "73") (name "P1.04") (class "Default")
      (node (ref "U1") (pin "P$U24") (pinfunction "P1.04_P$U24") (pintype "bidirectional"))
    )
    (net (code "74") (name "P1.05") (class "Default")
      (node (ref "U1") (pin "P$T23") (pinfunction "P1.05_P$T23") (pintype "bidirectional"))
    )
    (net (code "75") (name "P1.06") (class "Default")
      (node (ref "U1") (pin "P$R24") (pinfunction "P1.06_P$R24") (pintype "bidirectional"))
    )
    (net (code "76") (name "P1.07") (class "Default")
      (node (ref "U1") (pin "P$P23") (pinfunction "P1.07_P$P23") (pintype "bidirectional"))
    )
    (net (code "77") (name "P1.09") (class "Default")
      (node (ref "U1") (pin "P$R1") (pinfunction "P1.09_P$R1") (pintype "bidirectional"))
    )
    (net (code "78") (name "P1.10") (class "Default")
      (node (ref "U1") (pin "P$A20") (pinfunction "P1.10_P$A20") (pintype "bidirectional"))
    )
    (net (code "79") (name "P1.11") (class "Default")
      (node (ref "U1") (pin "P$B19") (pinfunction "P1.11_P$B19") (pintype "bidirectional"))
    )
    (net (code "80") (name "P1.12") (class "Default")
      (node (ref "U1") (pin "P$B17") (pinfunction "P1.12_P$B17") (pintype "bidirectional"))
    )
    (net (code "81") (name "P1.13") (class "Default")
      (node (ref "U1") (pin "P$A16") (pinfunction "P1.13_P$A16") (pintype "bidirectional"))
    )
    (net (code "82") (name "P1.14") (class "Default")
      (node (ref "U1") (pin "P$B15") (pinfunction "P1.14_P$B15") (pintype "bidirectional"))
    )
    (net (code "83") (name "P1.15") (class "Default")
      (node (ref "U1") (pin "P$A14") (pinfunction "P1.15_P$A14") (pintype "bidirectional"))
    )
    (net (code "84") (name "PMIC_INT") (class "Default")
      (node (ref "IC1") (pin "A1") (pinfunction "~{INT}_A1") (pintype "bidirectional"))
      (node (ref "U1") (pin "P$T2") (pinfunction "P0.11_P$T2") (pintype "bidirectional"))
    )
    (net (code "85") (name "PREVGH") (class "Default")
      (node (ref "D5") (pin "1") (pinfunction "K_1") (pintype "bidirectional"))
      (node (ref "EPD_C9") (pin "2") (pinfunction "2_2") (pintype "passive"))
      (node (ref "J1") (pin "21") (pinfunction "21_21") (pintype "bidirectional"))
    )
    (net (code "86") (name "PREVGL") (class "Default")
      (node (ref "D2") (pin "2") (pinfunction "A_2") (pintype "bidirectional"))
      (node (ref "EPD_C11") (pin "2") (pinfunction "2_2") (pintype "passive"))
      (node (ref "J1") (pin "23") (pinfunction "23_23") (pintype "bidirectional"))
    )
    (net (code "87") (name "RESE") (class "Default")
      (node (ref "J1") (pin "3") (pinfunction "3_3") (pintype "bidirectional"))
      (node (ref "Q3") (pin "2") (pinfunction "S_2") (pintype "bidirectional"))
      (node (ref "R1_EP_DR") (pin "2") (pinfunction "2_2") (pintype "bidirectional"))
    )
    (net (code "88") (name "RESET") (class "Default")
      (node (ref "J2") (pin "6") (pinfunction "6_6") (pintype "bidirectional"))
      (node (ref "TP_RESET") (pin "TP") (pinfunction "TP_TP") (pintype "input"))
      (node (ref "U1") (pin "P$AC13") (pinfunction "P0.18/RESET_P$AC13") (pintype "bidirectional"))
    )
    (net (code "89") (name "SCK") (class "Default")
      (node (ref "J1") (pin "13") (pinfunction "13_13") (pintype "bidirectional"))
      (node (ref "U1") (pin "P$A12") (pinfunction "P0.02/AIN0_P$A12") (pintype "bidirectional"))
    )
    (net (code "90") (name "SCL") (class "Default")
      (node (ref "IC1") (pin "B1") (pinfunction "SCL_B1") (pintype "bidirectional"))
      (node (ref "IC2") (pin "C1") (pinfunction "SCL_C1") (pintype "bidirectional"))
      (node (ref "IC3") (pin "12") (pinfunction "SCX_12") (pintype "bidirectional"))
      (node (ref "R17") (pin "2") (pinfunction "2_2") (pintype "bidirectional"))
      (node (ref "R4") (pin "1") (pinfunction "1_1") (pintype "bidirectional"))
      (node (ref "TP_SCL") (pin "TP") (pinfunction "TP_TP") (pintype "input"))
      (node (ref "U1") (pin "P$M2") (pinfunction "P0.07_P$M2") (pintype "bidirectional"))
      (node (ref "U3") (pin "7") (pinfunction "SCL_7") (pintype "input"))
    )
    (net (code "91") (name "SDA") (class "Default")
      (node (ref "IC1") (pin "C1") (pinfunction "SDA_C1") (pintype "bidirectional"))
      (node (ref "IC2") (pin "B2") (pinfunction "SDA_B2") (pintype "bidirectional"))
      (node (ref "IC3") (pin "2") (pinfunction "SDX_2") (pintype "bidirectional"))
      (node (ref "R18") (pin "2") (pinfunction "2_2") (pintype "bidirectional"))
      (node (ref "R2") (pin "1") (pinfunction "1_1") (pintype "bidirectional"))
      (node (ref "TP_SDA") (pin "TP") (pinfunction "TP_TP") (pintype "input"))
      (node (ref "U1") (pin "P$L1") (pinfunction "P0.06_P$L1") (pintype "bidirectional"))
      (node (ref "U3") (pin "8") (pinfunction "SDA_8") (pintype "bidirectional"))
    )
    (net (code "92") (name "SWDCLK") (class "Default")
      (node (ref "J2") (pin "4") (pinfunction "4_4") (pintype "bidirectional"))
      (node (ref "TP_SWDCLK") (pin "TP") (pinfunction "TP_TP") (pintype "input"))
      (node (ref "U1") (pin "P$AA24") (pinfunction "SWDCLK_P$AA24") (pintype "input"))
    )
    (net (code "93") (name "SWDIO") (class "Default")
      (node (ref "J2") (pin "2") (pinfunction "2_2") (pintype "bidirectional"))
      (node (ref "TP_SWDIO") (pin "TP") (pinfunction "TP_TP") (pintype "input"))
      (node (ref "U1") (pin "P$AC24") (pinfunction "SWDIO_P$AC24") (pintype "bidirectional"))
    )
    (net (code "94") (name "SWO") (class "Default")
      (node (ref "TP_SWO") (pin "TP") (pinfunction "TP_TP") (pintype "input"))
      (node (ref "U1") (pin "P$AD22") (pinfunction "P1.00_P$AD22") (pintype "bidirectional"))
    )
    (net (code "95") (name "VBAT") (class "Default")
      (node (ref "C27") (pin "2") (pinfunction "2_2") (pintype "passive"))
      (node (ref "C37") (pin "1") (pinfunction "1_1") (pintype "passive"))
      (node (ref "IC1") (pin "C2") (pinfunction "BAT_C2") (pintype "bidirectional"))
      (node (ref "TP_VBAT") (pin "TP") (pinfunction "TP_TP") (pintype "input"))
      (node (ref "U3") (pin "2") (pinfunction "CELL_2") (pintype "power_in"))
      (node (ref "U3") (pin "3") (pinfunction "VDD_3") (pintype "power_in"))
    )
    (net (code "96") (name "VBUS") (class "Default")
      (node (ref "C21") (pin "1") (pinfunction "1_1") (pintype "passive"))
      (node (ref "C38") (pin "1") (pinfunction "1_1") (pintype "passive"))
      (node (ref "C42") (pin "1") (pinfunction "1_1") (pintype "passive"))
      (node (ref "C43") (pin "1") (pinfunction "1_1") (pintype "passive"))
      (node (ref "D3") (pin "5") (pinfunction "VBUS_5") (pintype "bidirectional"))
      (node (ref "IC1") (pin "A2") (pinfunction "IN_A2") (pintype "bidirectional"))
      (node (ref "J4") (pin "A4_B9") (pinfunction "VBUS_A4_B9") (pintype "power_in"))
      (node (ref "J4") (pin "A9_B4") (pinfunction "VBUS_A9_B4") (pintype "power_in"))
      (node (ref "U1") (pin "P$AD2") (pinfunction "VBUS_P$AD2") (pintype "power_in"))
    )
    (net (code "97") (name "VREG") (class "Default")
      (node (ref "C23") (pin "2") (pinfunction "2_2") (pintype "passive"))
      (node (ref "C24") (pin "2") (pinfunction "2_2") (pintype "passive"))
      (node (ref "C39") (pin "1") (pinfunction "1_1") (pintype "passive"))
      (node (ref "IC1") (pin "B2") (pinfunction "SYS_B2") (pintype "bidirectional"))
      (node (ref "IC9") (pin "A1") (pinfunction "EN_A1") (pintype "bidirectional"))
      (node (ref "IC9") (pin "A2") (pinfunction "VIN_1_A2") (pintype "bidirectional"))
      (node (ref "IC9") (pin "A3") (pinfunction "VIN_2_A3") (pintype "bidirectional"))
      (node (ref "TP_VREG") (pin "TP") (pinfunction "TP_TP") (pintype "input"))
    )
    (net (code "98") (name "unconnected-(ANT1-NC-Pad2)") (class "Default")
      (node (ref "ANT1") (pin "2") (pinfunction "NC_2") (pintype "no_connect"))
    )
    (net (code "99") (name "unconnected-(IC3-ASCL-Pad11)") (class "Default")
      (node (ref "IC3") (pin "11") (pinfunction "ASCL_11") (pintype "bidirectional"))
    )
    (net (code "100") (name "unconnected-(IC3-ASDA-Pad4)") (class "Default")
      (node (ref "IC3") (pin "4") (pinfunction "ASDA_4") (pintype "bidirectional"))
    )
    (net (code "101") (name "unconnected-(J1-Pad1)") (class "Default")
      (node (ref "J1") (pin "1") (pinfunction "1_1") (pintype "bidirectional"))
    )
    (net (code "102") (name "unconnected-(J1-Pad6)") (class "Default")
      (node (ref "J1") (pin "6") (pinfunction "6_6") (pintype "bidirectional"))
    )
    (net (code "103") (name "unconnected-(J1-Pad7)") (class "Default")
      (node (ref "J1") (pin "7") (pinfunction "7_7") (pintype "bidirectional"))
    )
    (net (code "104") (name "unconnected-(J4-SBU1-PadA8)") (class "Default")
      (node (ref "J4") (pin "A8") (pinfunction "SBU1_A8") (pintype "bidirectional"))
    )
    (net (code "105") (name "unconnected-(J4-SBU2-PadB8)") (class "Default")
      (node (ref "J4") (pin "B8") (pinfunction "SBU2_B8") (pintype "bidirectional"))
    )
    (net (code "106") (name "unconnected-(U1-DCCH-PadP$AB2)") (class "Default")
      (node (ref "U1") (pin "P$AB2") (pinfunction "DCCH_P$AB2") (pintype "bidirectional"))
    )
  )
)
